# Filter.net
KiCad netlist of a schematic drawn in Altium Designer
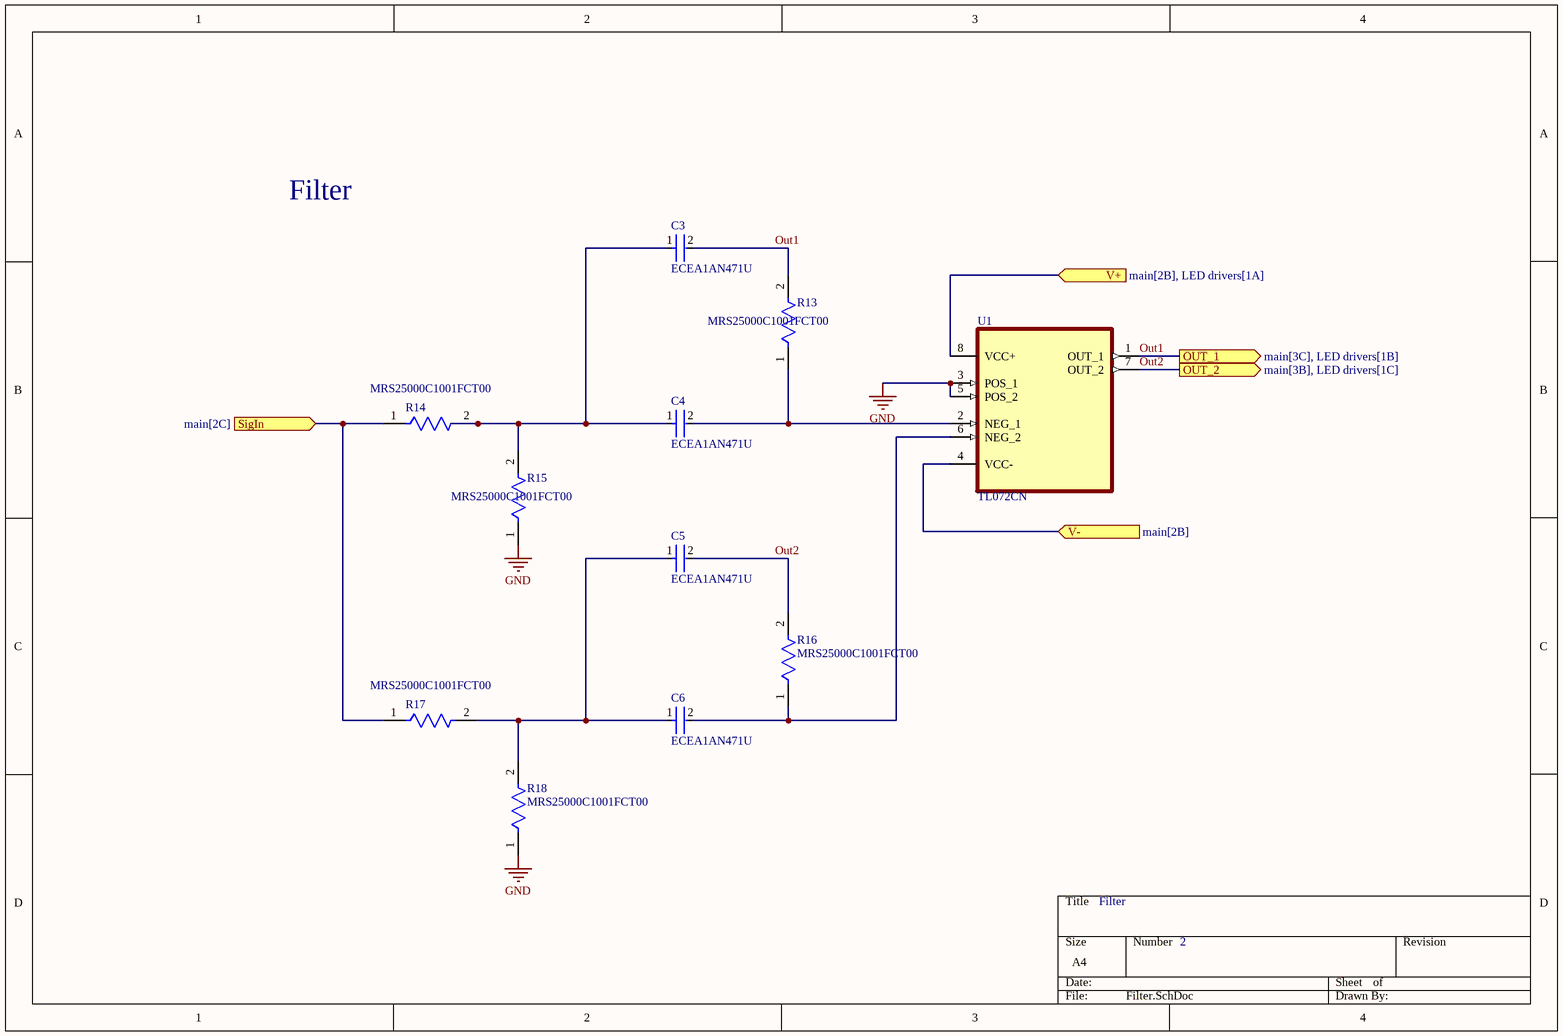
[diagram p0: Filter.SchDoc]

(export (version "E")
  (design (tool "Eeschema 10.0.6"))
  (components
    (comp (ref "C3")
      (value "ECEA1AN471U")
      (footprint "FP-RAD-TH-D_10_0_5-L_16_1-MFG")
      (description "Aluminum Electrolytic Capacitors (Radial Lead Type) 470uF ±20% 10V")
      (fields (field (name "TOLERANCE") "20%") (field (name "VOLTAGE") "10V"))
      (libsource (lib "Altium Content Vault") (part "02cd4be3c70576c341d710602a673aa"))
    )
    (comp (ref "C4")
      (value "ECEA1AN471U")
      (footprint "FP-RAD-TH-D_10_0_5-L_16_1-MFG")
      (description "Aluminum Electrolytic Capacitors (Radial Lead Type) 470uF ±20% 10V")
      (fields (field (name "TOLERANCE") "20%") (field (name "VOLTAGE") "10V"))
      (libsource (lib "Altium Content Vault") (part "02cd4be3c70576c341d710602a673aa"))
    )
    (comp (ref "C5")
      (value "ECEA1AN471U")
      (footprint "FP-RAD-TH-D_10_0_5-L_16_1-MFG")
      (description "Aluminum Electrolytic Capacitors (Radial Lead Type) 470uF ±20% 10V")
      (fields (field (name "TOLERANCE") "20%") (field (name "VOLTAGE") "10V"))
      (libsource (lib "Altium Content Vault") (part "02cd4be3c70576c341d710602a673aa"))
    )
    (comp (ref "C6")
      (value "ECEA1AN471U")
      (footprint "FP-RAD-TH-D_10_0_5-L_16_1-MFG")
      (description "Aluminum Electrolytic Capacitors (Radial Lead Type) 470uF ±20% 10V")
      (fields (field (name "TOLERANCE") "20%") (field (name "VOLTAGE") "10V"))
      (libsource (lib "Altium Content Vault") (part "02cd4be3c70576c341d710602a673aa"))
    )
    (comp (ref "R13")
      (value "MRS25000C1001FCT00")
      (footprint "FP-MRS25-MFG")
      (description "RES 1K OHM 0.6W 1% AXIAL")
      (fields (field (name "TOLERANCE") "1%"))
      (libsource (lib "Altium Content Vault") (part "1029c3af85768c4190bb7ad29bc67b5"))
    )
    (comp (ref "R14")
      (value "MRS25000C1001FCT00")
      (footprint "FP-MRS25-MFG")
      (description "RES 1K OHM 0.6W 1% AXIAL")
      (fields (field (name "TOLERANCE") "1%"))
      (libsource (lib "Altium Content Vault") (part "1029c3af85768c4190bb7ad29bc67b5"))
    )
    (comp (ref "R15")
      (value "MRS25000C1001FCT00")
      (footprint "FP-MRS25-MFG")
      (description "RES 1K OHM 0.6W 1% AXIAL")
      (fields (field (name "TOLERANCE") "1%"))
      (libsource (lib "Altium Content Vault") (part "1029c3af85768c4190bb7ad29bc67b5"))
    )
    (comp (ref "R16")
      (value "MRS25000C1001FCT00")
      (footprint "FP-MRS25-MFG")
      (description "RES 1K OHM 0.6W 1% AXIAL")
      (fields (field (name "TOLERANCE") "1%"))
      (libsource (lib "Altium Content Vault") (part "1029c3af85768c4190bb7ad29bc67b5"))
    )
    (comp (ref "R17")
      (value "MRS25000C1001FCT00")
      (footprint "FP-MRS25-MFG")
      (description "RES 1K OHM 0.6W 1% AXIAL")
      (fields (field (name "TOLERANCE") "1%"))
      (libsource (lib "Altium Content Vault") (part "1029c3af85768c4190bb7ad29bc67b5"))
    )
    (comp (ref "R18")
      (value "MRS25000C1001FCT00")
      (footprint "FP-MRS25-MFG")
      (description "RES 1K OHM 0.6W 1% AXIAL")
      (fields (field (name "TOLERANCE") "1%"))
      (libsource (lib "Altium Content Vault") (part "1029c3af85768c4190bb7ad29bc67b5"))
    )
    (comp (ref "U1")
      (value "TL072CN")
      (footprint "DIP254P762X533-8")
      (description "J-FET Amplifier 2 Circuit 8-DIP")
      (fields (field (name "MF") "Texas Instruments"))
      (libsource (lib "TL072CN") (part "TL072CN"))
    )
  )
  (nets
    (net (code "1") (name "/Out1") (class "Default")
      (node (ref "C3") (pin "2") (pinfunction "2_2") (pintype "passive"))
      (node (ref "R13") (pin "2") (pinfunction "2_2") (pintype "passive"))
      (node (ref "U1") (pin "1") (pinfunction "OUT_1_1") (pintype "output"))
    )
    (net (code "2") (name "/Out2") (class "Default")
      (node (ref "C5") (pin "2") (pinfunction "2_2") (pintype "passive"))
      (node (ref "R16") (pin "2") (pinfunction "2_2") (pintype "passive"))
      (node (ref "U1") (pin "7") (pinfunction "OUT_2_7") (pintype "output"))
    )
    (net (code "3") (name "/SigIn") (class "Default")
      (node (ref "R14") (pin "1") (pinfunction "1_1") (pintype "passive"))
      (node (ref "R17") (pin "1") (pinfunction "1_1") (pintype "passive"))
    )
    (net (code "4") (name "/V+") (class "Default")
      (node (ref "U1") (pin "8") (pinfunction "VCC+_8") (pintype "power_in"))
    )
    (net (code "5") (name "/V-") (class "Default")
      (node (ref "U1") (pin "4") (pinfunction "VCC-_4") (pintype "power_in"))
    )
    (net (code "6") (name "GND") (class "Default")
      (node (ref "R15") (pin "1") (pinfunction "1_1") (pintype "passive"))
      (node (ref "R18") (pin "1") (pinfunction "1_1") (pintype "passive"))
      (node (ref "U1") (pin "3") (pinfunction "POS_1_3") (pintype "input"))
      (node (ref "U1") (pin "5") (pinfunction "POS_2_5") (pintype "input"))
    )
    (net (code "7") (name "Net-(C3-Pad1)") (class "Default")
      (node (ref "C3") (pin "1") (pinfunction "1_1") (pintype "passive"))
      (node (ref "C4") (pin "1") (pinfunction "1_1") (pintype "passive"))
      (node (ref "R14") (pin "2") (pinfunction "2_2") (pintype "passive"))
      (node (ref "R15") (pin "2") (pinfunction "2_2") (pintype "passive"))
    )
    (net (code "8") (name "Net-(C5-Pad1)") (class "Default")
      (node (ref "C5") (pin "1") (pinfunction "1_1") (pintype "passive"))
      (node (ref "C6") (pin "1") (pinfunction "1_1") (pintype "passive"))
      (node (ref "R17") (pin "2") (pinfunction "2_2") (pintype "passive"))
      (node (ref "R18") (pin "2") (pinfunction "2_2") (pintype "passive"))
    )
    (net (code "9") (name "Net-(U1-NEG_1)") (class "Default")
      (node (ref "C4") (pin "2") (pinfunction "2_2") (pintype "passive"))
      (node (ref "R13") (pin "1") (pinfunction "1_1") (pintype "passive"))
      (node (ref "U1") (pin "2") (pinfunction "NEG_1_2") (pintype "input"))
    )
    (net (code "10") (name "Net-(U1-NEG_2)") (class "Default")
      (node (ref "C6") (pin "2") (pinfunction "2_2") (pintype "passive"))
      (node (ref "R16") (pin "1") (pinfunction "1_1") (pintype "passive"))
      (node (ref "U1") (pin "6") (pinfunction "NEG_2_6") (pintype "input"))
    )
  )
)
